# main.net
KiCad netlist of a schematic drawn in EAGLE
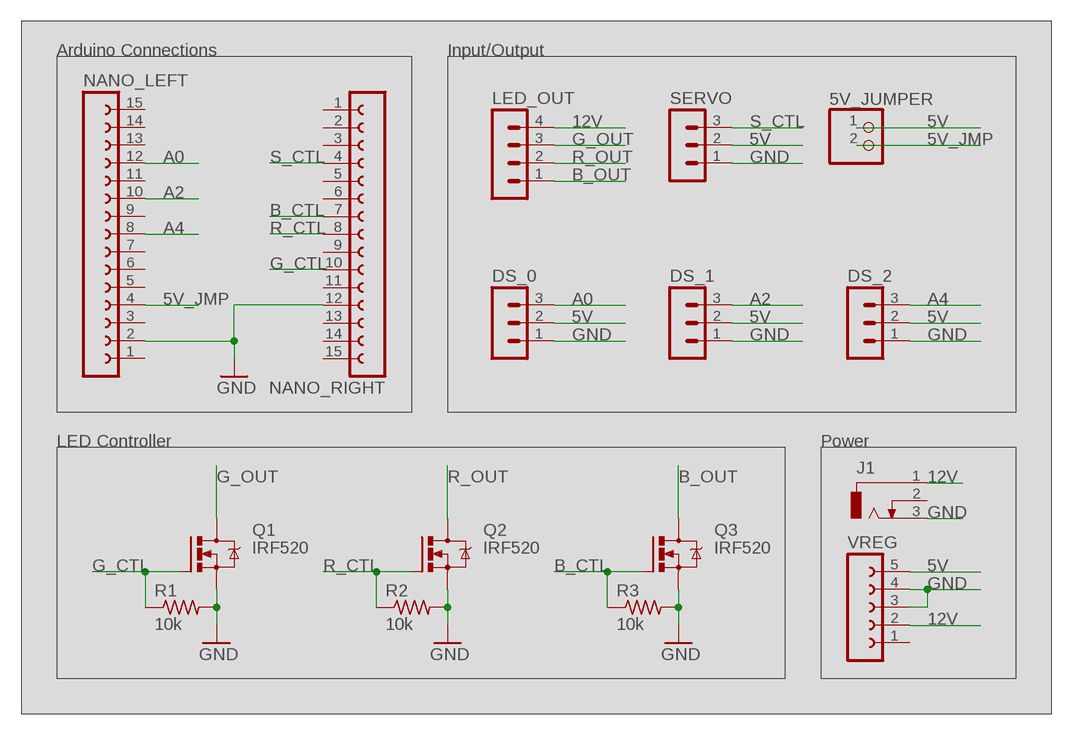
[diagram p0: schematic, sheet 1]

(export (version "E")
  (design (tool "Eeschema 10.0.6"))
  (components
    (comp (ref "5V_JUMPER")
      (value "PINHD-1X2")
      (footprint "eagle-import:1X02")
      (libsource (lib "eagle-import") (part "PINHD-1X2"))
    )
    (comp (ref "DS_0")
      (value "MA03-1")
      (footprint "eagle-import:MA03-1")
      (libsource (lib "eagle-import") (part "MA03-1"))
    )
    (comp (ref "DS_1")
      (value "MA03-1")
      (footprint "eagle-import:MA03-1")
      (libsource (lib "eagle-import") (part "MA03-1"))
    )
    (comp (ref "DS_2")
      (value "MA03-1")
      (footprint "eagle-import:MA03-1")
      (libsource (lib "eagle-import") (part "MA03-1"))
    )
    (comp (ref "J1")
      (value "DCJ0303")
      (footprint "eagle-import:DCJ0303")
      (libsource (lib "eagle-import") (part "DCJ0303"))
    )
    (comp (ref "LED_OUT")
      (value "MA04-1")
      (footprint "eagle-import:MA04-1")
      (libsource (lib "eagle-import") (part "MA04-1"))
    )
    (comp (ref "NANO_LEFT")
      (value "FE15-1")
      (footprint "eagle-import:FE15")
      (libsource (lib "eagle-import") (part "FE15-1"))
    )
    (comp (ref "NANO_RIGHT")
      (value "FE15-1")
      (footprint "eagle-import:FE15")
      (libsource (lib "eagle-import") (part "FE15-1"))
    )
    (comp (ref "Q1")
      (value "IRF520")
      (footprint "eagle-import:TO220BV")
      (libsource (lib "eagle-import") (part "IRF520"))
    )
    (comp (ref "Q2")
      (value "IRF520")
      (footprint "eagle-import:TO220BV")
      (libsource (lib "eagle-import") (part "IRF520"))
    )
    (comp (ref "Q3")
      (value "IRF520")
      (footprint "eagle-import:TO220BV")
      (libsource (lib "eagle-import") (part "IRF520"))
    )
    (comp (ref "R1")
      (value "10k")
      (footprint "eagle-import:0207_7")
      (libsource (lib "eagle-import") (part "R-US_0207/7"))
    )
    (comp (ref "R2")
      (value "10k")
      (footprint "eagle-import:0207_7")
      (libsource (lib "eagle-import") (part "R-US_0207/7"))
    )
    (comp (ref "R3")
      (value "10k")
      (footprint "eagle-import:0207_7")
      (libsource (lib "eagle-import") (part "R-US_0207/7"))
    )
    (comp (ref "SERVO")
      (value "MA03-1")
      (footprint "eagle-import:MA03-1")
      (libsource (lib "eagle-import") (part "MA03-1"))
    )
    (comp (ref "VREG")
      (value "FE05W")
      (footprint "eagle-import:FE05W")
      (libsource (lib "eagle-import") (part "FE05W"))
    )
  )
  (nets
    (net (code "1") (name "/5V") (class "Default")
      (node (ref "5V_JUMPER") (pin "1") (pinfunction "1_1") (pintype "passive"))
      (node (ref "DS_0") (pin "2") (pinfunction "2_2") (pintype "passive"))
      (node (ref "DS_1") (pin "2") (pinfunction "2_2") (pintype "passive"))
      (node (ref "DS_2") (pin "2") (pinfunction "2_2") (pintype "passive"))
      (node (ref "SERVO") (pin "2") (pinfunction "2_2") (pintype "passive"))
      (node (ref "VREG") (pin "5") (pinfunction "5_5") (pintype "passive"))
    )
    (net (code "2") (name "/5V_JMP") (class "Default")
      (node (ref "5V_JUMPER") (pin "2") (pinfunction "2_2") (pintype "passive"))
      (node (ref "NANO_LEFT") (pin "4") (pinfunction "4_4") (pintype "passive"))
    )
    (net (code "3") (name "/12V") (class "Default")
      (node (ref "J1") (pin "1") (pinfunction "1_1") (pintype "passive"))
      (node (ref "LED_OUT") (pin "4") (pinfunction "4_4") (pintype "passive"))
      (node (ref "VREG") (pin "2") (pinfunction "2_2") (pintype "passive"))
    )
    (net (code "4") (name "/A0") (class "Default")
      (node (ref "DS_0") (pin "3") (pinfunction "3_3") (pintype "passive"))
      (node (ref "NANO_LEFT") (pin "12") (pinfunction "12_12") (pintype "passive"))
    )
    (net (code "5") (name "/A2") (class "Default")
      (node (ref "DS_1") (pin "3") (pinfunction "3_3") (pintype "passive"))
      (node (ref "NANO_LEFT") (pin "10") (pinfunction "10_10") (pintype "passive"))
    )
    (net (code "6") (name "/A4") (class "Default")
      (node (ref "DS_2") (pin "3") (pinfunction "3_3") (pintype "passive"))
      (node (ref "NANO_LEFT") (pin "8") (pinfunction "8_8") (pintype "passive"))
    )
    (net (code "7") (name "/B_CTL") (class "Default")
      (node (ref "NANO_RIGHT") (pin "7") (pinfunction "7_7") (pintype "passive"))
      (node (ref "Q3") (pin "G") (pinfunction "G_G") (pintype "passive"))
      (node (ref "R3") (pin "1") (pinfunction "1_1") (pintype "passive"))
    )
    (net (code "8") (name "/B_OUT") (class "Default")
      (node (ref "LED_OUT") (pin "1") (pinfunction "1_1") (pintype "passive"))
      (node (ref "Q3") (pin "D") (pinfunction "D_D") (pintype "passive"))
    )
    (net (code "9") (name "/G_CTL") (class "Default")
      (node (ref "NANO_RIGHT") (pin "10") (pinfunction "10_10") (pintype "passive"))
      (node (ref "Q1") (pin "G") (pinfunction "G_G") (pintype "passive"))
      (node (ref "R1") (pin "1") (pinfunction "1_1") (pintype "passive"))
    )
    (net (code "10") (name "/G_OUT") (class "Default")
      (node (ref "LED_OUT") (pin "3") (pinfunction "3_3") (pintype "passive"))
      (node (ref "Q1") (pin "D") (pinfunction "D_D") (pintype "passive"))
    )
    (net (code "11") (name "/R_CTL") (class "Default")
      (node (ref "NANO_RIGHT") (pin "8") (pinfunction "8_8") (pintype "passive"))
      (node (ref "Q2") (pin "G") (pinfunction "G_G") (pintype "passive"))
      (node (ref "R2") (pin "1") (pinfunction "1_1") (pintype "passive"))
    )
    (net (code "12") (name "/R_OUT") (class "Default")
      (node (ref "LED_OUT") (pin "2") (pinfunction "2_2") (pintype "passive"))
      (node (ref "Q2") (pin "D") (pinfunction "D_D") (pintype "passive"))
    )
    (net (code "13") (name "/S_CTL") (class "Default")
      (node (ref "NANO_RIGHT") (pin "4") (pinfunction "4_4") (pintype "passive"))
      (node (ref "SERVO") (pin "3") (pinfunction "3_3") (pintype "passive"))
    )
    (net (code "14") (name "GND") (class "Default")
      (node (ref "DS_0") (pin "1") (pinfunction "1_1") (pintype "passive"))
      (node (ref "DS_1") (pin "1") (pinfunction "1_1") (pintype "passive"))
      (node (ref "DS_2") (pin "1") (pinfunction "1_1") (pintype "passive"))
      (node (ref "J1") (pin "3") (pinfunction "3_3") (pintype "passive"))
      (node (ref "NANO_LEFT") (pin "2") (pinfunction "2_2") (pintype "passive"))
      (node (ref "NANO_RIGHT") (pin "12") (pinfunction "12_12") (pintype "passive"))
      (node (ref "Q1") (pin "S") (pinfunction "S_S") (pintype "passive"))
      (node (ref "Q2") (pin "S") (pinfunction "S_S") (pintype "passive"))
      (node (ref "Q3") (pin "S") (pinfunction "S_S") (pintype "passive"))
      (node (ref "R1") (pin "2") (pinfunction "2_2") (pintype "passive"))
      (node (ref "R2") (pin "2") (pinfunction "2_2") (pintype "passive"))
      (node (ref "R3") (pin "2") (pinfunction "2_2") (pintype "passive"))
      (node (ref "SERVO") (pin "1") (pinfunction "1_1") (pintype "passive"))
      (node (ref "VREG") (pin "3") (pinfunction "3_3") (pintype "passive"))
      (node (ref "VREG") (pin "4") (pinfunction "4_4") (pintype "passive"))
    )
    (net (code "15") (name "unconnected-(J1-Pad2)") (class "Default")
      (node (ref "J1") (pin "2") (pinfunction "2_2") (pintype "passive"))
    )
    (net (code "16") (name "unconnected-(NANO_LEFT-Pad1)") (class "Default")
      (node (ref "NANO_LEFT") (pin "1") (pinfunction "1_1") (pintype "passive"))
    )
    (net (code "17") (name "unconnected-(NANO_LEFT-Pad3)") (class "Default")
      (node (ref "NANO_LEFT") (pin "3") (pinfunction "3_3") (pintype "passive"))
    )
    (net (code "18") (name "unconnected-(NANO_LEFT-Pad5)") (class "Default")
      (node (ref "NANO_LEFT") (pin "5") (pinfunction "5_5") (pintype "passive"))
    )
    (net (code "19") (name "unconnected-(NANO_LEFT-Pad6)") (class "Default")
      (node (ref "NANO_LEFT") (pin "6") (pinfunction "6_6") (pintype "passive"))
    )
    (net (code "20") (name "unconnected-(NANO_LEFT-Pad7)") (class "Default")
      (node (ref "NANO_LEFT") (pin "7") (pinfunction "7_7") (pintype "passive"))
    )
    (net (code "21") (name "unconnected-(NANO_LEFT-Pad9)") (class "Default")
      (node (ref "NANO_LEFT") (pin "9") (pinfunction "9_9") (pintype "passive"))
    )
    (net (code "22") (name "unconnected-(NANO_LEFT-Pad11)") (class "Default")
      (node (ref "NANO_LEFT") (pin "11") (pinfunction "11_11") (pintype "passive"))
    )
    (net (code "23") (name "unconnected-(NANO_LEFT-Pad13)") (class "Default")
      (node (ref "NANO_LEFT") (pin "13") (pinfunction "13_13") (pintype "passive"))
    )
    (net (code "24") (name "unconnected-(NANO_LEFT-Pad14)") (class "Default")
      (node (ref "NANO_LEFT") (pin "14") (pinfunction "14_14") (pintype "passive"))
    )
    (net (code "25") (name "unconnected-(NANO_LEFT-Pad15)") (class "Default")
      (node (ref "NANO_LEFT") (pin "15") (pinfunction "15_15") (pintype "passive"))
    )
    (net (code "26") (name "unconnected-(NANO_RIGHT-Pad1)") (class "Default")
      (node (ref "NANO_RIGHT") (pin "1") (pinfunction "1_1") (pintype "passive"))
    )
    (net (code "27") (name "unconnected-(NANO_RIGHT-Pad2)") (class "Default")
      (node (ref "NANO_RIGHT") (pin "2") (pinfunction "2_2") (pintype "passive"))
    )
    (net (code "28") (name "unconnected-(NANO_RIGHT-Pad3)") (class "Default")
      (node (ref "NANO_RIGHT") (pin "3") (pinfunction "3_3") (pintype "passive"))
    )
    (net (code "29") (name "unconnected-(NANO_RIGHT-Pad5)") (class "Default")
      (node (ref "NANO_RIGHT") (pin "5") (pinfunction "5_5") (pintype "passive"))
    )
    (net (code "30") (name "unconnected-(NANO_RIGHT-Pad6)") (class "Default")
      (node (ref "NANO_RIGHT") (pin "6") (pinfunction "6_6") (pintype "passive"))
    )
    (net (code "31") (name "unconnected-(NANO_RIGHT-Pad9)") (class "Default")
      (node (ref "NANO_RIGHT") (pin "9") (pinfunction "9_9") (pintype "passive"))
    )
    (net (code "32") (name "unconnected-(NANO_RIGHT-Pad11)") (class "Default")
      (node (ref "NANO_RIGHT") (pin "11") (pinfunction "11_11") (pintype "passive"))
    )
    (net (code "33") (name "unconnected-(NANO_RIGHT-Pad13)") (class "Default")
      (node (ref "NANO_RIGHT") (pin "13") (pinfunction "13_13") (pintype "passive"))
    )
    (net (code "34") (name "unconnected-(NANO_RIGHT-Pad14)") (class "Default")
      (node (ref "NANO_RIGHT") (pin "14") (pinfunction "14_14") (pintype "passive"))
    )
    (net (code "35") (name "unconnected-(NANO_RIGHT-Pad15)") (class "Default")
      (node (ref "NANO_RIGHT") (pin "15") (pinfunction "15_15") (pintype "passive"))
    )
    (net (code "36") (name "unconnected-(VREG-Pad1)") (class "Default")
      (node (ref "VREG") (pin "1") (pinfunction "1_1") (pintype "passive"))
    )
  )
)
